# M401B.net
KiCad netlist of a schematic drawn in EAGLE
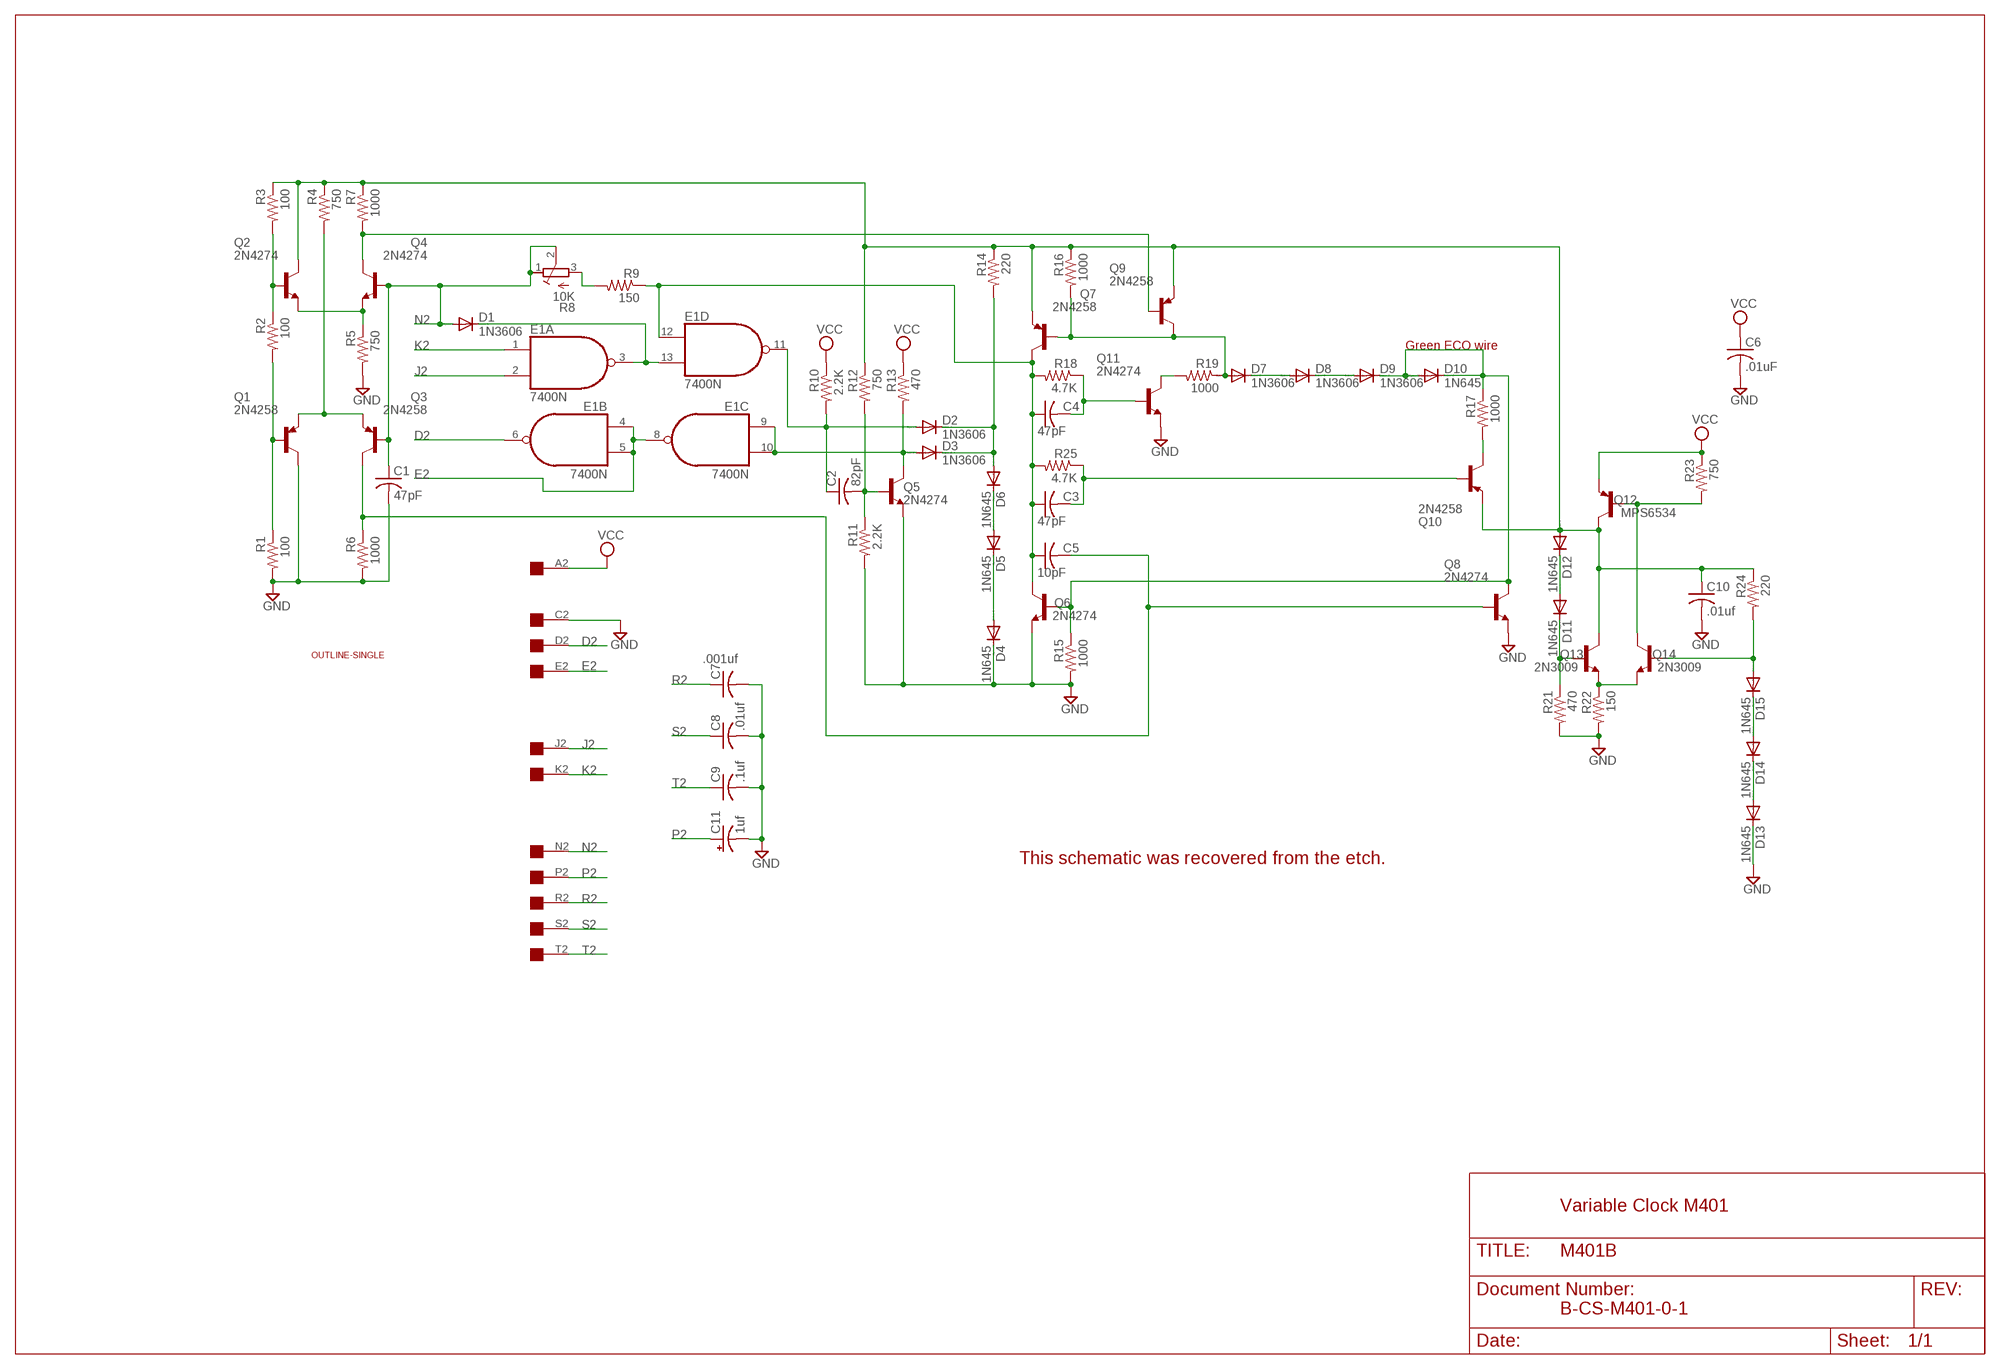
[diagram p0: schematic, sheet 1]

(export (version "E")
  (design (tool "Eeschema 10.0.6"))
  (components
    (comp (ref "C1")
      (value "47pF")
      (footprint "eagle-import:C050-025X075")
      (libsource (lib "eagle-import") (part "C-US050-025X075"))
    )
    (comp (ref "C2")
      (value "82pF")
      (footprint "eagle-import:C050-025X075")
      (libsource (lib "eagle-import") (part "C-US050-025X075"))
    )
    (comp (ref "C3")
      (value "47pF")
      (footprint "eagle-import:C050-025X075")
      (libsource (lib "eagle-import") (part "C-US050-025X075"))
    )
    (comp (ref "C4")
      (value "47pF")
      (footprint "eagle-import:C050-025X075")
      (libsource (lib "eagle-import") (part "C-US050-025X075"))
    )
    (comp (ref "C5")
      (value "10pF")
      (footprint "eagle-import:C225-062X268")
      (libsource (lib "eagle-import") (part "C-US225-062X268"))
    )
    (comp (ref "C6")
      (value ".01uF")
      (footprint "eagle-import:C050-025X075")
      (libsource (lib "eagle-import") (part "C-US050-025X075"))
    )
    (comp (ref "C7")
      (value ".001uf")
      (footprint "eagle-import:C050-025X075")
      (libsource (lib "eagle-import") (part "C-US050-025X075"))
    )
    (comp (ref "C8")
      (value ".01uf")
      (footprint "eagle-import:C225-062X268")
      (libsource (lib "eagle-import") (part "C-US225-062X268"))
    )
    (comp (ref "C9")
      (value ".1uf")
      (footprint "eagle-import:C275-093X316")
      (libsource (lib "eagle-import") (part "C-US275-093X316"))
    )
    (comp (ref "C10")
      (value ".01uf")
      (footprint "eagle-import:C050-025X075")
      (libsource (lib "eagle-import") (part "C-US050-025X075"))
    )
    (comp (ref "C11")
      (value "1uf")
      (footprint "eagle-import:E15-5")
      (libsource (lib "eagle-import") (part "CPOL-USE15-5AXIAL"))
    )
    (comp (ref "D1")
      (value "1N3606")
      (footprint "eagle-import:DO35-10")
      (libsource (lib "eagle-import") (part "1N4148DO35-10"))
    )
    (comp (ref "D2")
      (value "1N3606")
      (footprint "eagle-import:DO35-10")
      (libsource (lib "eagle-import") (part "1N4148DO35-10"))
    )
    (comp (ref "D3")
      (value "1N3606")
      (footprint "eagle-import:DO35-10")
      (libsource (lib "eagle-import") (part "1N4148DO35-10"))
    )
    (comp (ref "D4")
      (value "1N645")
      (footprint "eagle-import:DO35-10")
      (libsource (lib "eagle-import") (part "1N4148DO35-10"))
    )
    (comp (ref "D5")
      (value "1N645")
      (footprint "eagle-import:DO35-10")
      (libsource (lib "eagle-import") (part "1N4148DO35-10"))
    )
    (comp (ref "D6")
      (value "1N645")
      (footprint "eagle-import:DO35-10")
      (libsource (lib "eagle-import") (part "1N4148DO35-10"))
    )
    (comp (ref "D7")
      (value "1N3606")
      (footprint "eagle-import:DO35-10")
      (libsource (lib "eagle-import") (part "1N4148DO35-10"))
    )
    (comp (ref "D8")
      (value "1N3606")
      (footprint "eagle-import:DO35-10")
      (libsource (lib "eagle-import") (part "1N4148DO35-10"))
    )
    (comp (ref "D9")
      (value "1N3606")
      (footprint "eagle-import:DO35-10")
      (libsource (lib "eagle-import") (part "1N4148DO35-10"))
    )
    (comp (ref "D10")
      (value "1N645")
      (footprint "eagle-import:DO35-10")
      (libsource (lib "eagle-import") (part "1N4148DO35-10"))
    )
    (comp (ref "D11")
      (value "1N645")
      (footprint "eagle-import:DO35-10")
      (libsource (lib "eagle-import") (part "1N4148DO35-10"))
    )
    (comp (ref "D12")
      (value "1N645")
      (footprint "eagle-import:DO35-10")
      (libsource (lib "eagle-import") (part "1N4148DO35-10"))
    )
    (comp (ref "D13")
      (value "1N645")
      (footprint "eagle-import:DO35-10")
      (libsource (lib "eagle-import") (part "1N4148DO35-10"))
    )
    (comp (ref "D14")
      (value "1N645")
      (footprint "eagle-import:DO35-10")
      (libsource (lib "eagle-import") (part "1N4148DO35-10"))
    )
    (comp (ref "D15")
      (value "1N645")
      (footprint "eagle-import:DO35-10")
      (libsource (lib "eagle-import") (part "1N4148DO35-10"))
    )
    (comp (ref "E1")
      (value "7400N")
      (footprint "eagle-import:DIL14")
      (libsource (lib "eagle-import") (part "7400N"))
    )
    (comp (ref "Q1")
      (value "2N4258")
      (footprint "eagle-import:TO39")
      (libsource (lib "eagle-import") (part "-PNP-TO39-EBC2N3637"))
    )
    (comp (ref "Q2")
      (value "2N4274")
      (footprint "eagle-import:TO39")
      (libsource (lib "eagle-import") (part "-NPN-TO39-EBC2N3019"))
    )
    (comp (ref "Q3")
      (value "2N4258")
      (footprint "eagle-import:TO39")
      (libsource (lib "eagle-import") (part "-PNP-TO39-EBC2N3637"))
    )
    (comp (ref "Q4")
      (value "2N4274")
      (footprint "eagle-import:TO39")
      (libsource (lib "eagle-import") (part "-NPN-TO39-EBC2N3019"))
    )
    (comp (ref "Q5")
      (value "2N4274")
      (footprint "eagle-import:TO39")
      (libsource (lib "eagle-import") (part "-NPN-TO39-EBC2N3019"))
    )
    (comp (ref "Q6")
      (value "2N4274")
      (footprint "eagle-import:TO39")
      (libsource (lib "eagle-import") (part "-NPN-TO39-EBC2N3019"))
    )
    (comp (ref "Q7")
      (value "2N4258")
      (footprint "eagle-import:TO39")
      (libsource (lib "eagle-import") (part "-PNP-TO39-EBC2N3637"))
    )
    (comp (ref "Q8")
      (value "2N4274")
      (footprint "eagle-import:TO39")
      (libsource (lib "eagle-import") (part "-NPN-TO39-EBC2N3019"))
    )
    (comp (ref "Q9")
      (value "2N4258")
      (footprint "eagle-import:TO39")
      (libsource (lib "eagle-import") (part "-PNP-TO39-EBC2N3637"))
    )
    (comp (ref "Q10")
      (value "2N4258")
      (footprint "eagle-import:TO39")
      (libsource (lib "eagle-import") (part "-PNP-TO39-EBC2N3637"))
    )
    (comp (ref "Q11")
      (value "2N4274")
      (footprint "eagle-import:TO39")
      (libsource (lib "eagle-import") (part "-NPN-TO39-EBC2N3019"))
    )
    (comp (ref "Q12")
      (value "MPS6534")
      (footprint "eagle-import:TO39")
      (libsource (lib "eagle-import") (part "-PNP-TO39-EBC2N3637"))
    )
    (comp (ref "Q13")
      (value "2N3009")
      (footprint "eagle-import:TO39")
      (libsource (lib "eagle-import") (part "-NPN-TO39-EBC2N3019"))
    )
    (comp (ref "Q14")
      (value "2N3009")
      (footprint "eagle-import:TO39")
      (libsource (lib "eagle-import") (part "-NPN-TO39-EBC2N3019"))
    )
    (comp (ref "R1")
      (value "100")
      (footprint "eagle-import:0207_10")
      (libsource (lib "eagle-import") (part "R-US_0207/10"))
    )
    (comp (ref "R2")
      (value "100")
      (footprint "eagle-import:0207_10")
      (libsource (lib "eagle-import") (part "R-US_0207/10"))
    )
    (comp (ref "R3")
      (value "100")
      (footprint "eagle-import:0207_10")
      (libsource (lib "eagle-import") (part "R-US_0207/10"))
    )
    (comp (ref "R4")
      (value "750")
      (footprint "eagle-import:0207_10")
      (libsource (lib "eagle-import") (part "R-US_0207/10"))
    )
    (comp (ref "R5")
      (value "750")
      (footprint "eagle-import:0207_10")
      (libsource (lib "eagle-import") (part "R-US_0207/10"))
    )
    (comp (ref "R6")
      (value "1000")
      (footprint "eagle-import:0207_10")
      (libsource (lib "eagle-import") (part "R-US_0207/10"))
    )
    (comp (ref "R7")
      (value "1000")
      (footprint "eagle-import:0207_10")
      (libsource (lib "eagle-import") (part "R-US_0207/10"))
    )
    (comp (ref "R8")
      (value "10K")
      (footprint "eagle-import:3006Y")
      (libsource (lib "eagle-import") (part "275P"))
    )
    (comp (ref "R9")
      (value "150")
      (footprint "eagle-import:0207_10")
      (libsource (lib "eagle-import") (part "R-US_0207/10"))
    )
    (comp (ref "R10")
      (value "2.2K")
      (footprint "eagle-import:0207_10")
      (libsource (lib "eagle-import") (part "R-US_0207/10"))
    )
    (comp (ref "R11")
      (value "2.2K")
      (footprint "eagle-import:0207_10")
      (libsource (lib "eagle-import") (part "R-US_0207/10"))
    )
    (comp (ref "R12")
      (value "750")
      (footprint "eagle-import:0207_10")
      (libsource (lib "eagle-import") (part "R-US_0207/10"))
    )
    (comp (ref "R13")
      (value "470")
      (footprint "eagle-import:0207_10")
      (libsource (lib "eagle-import") (part "R-US_0207/10"))
    )
    (comp (ref "R14")
      (value "220")
      (footprint "eagle-import:0207_10")
      (libsource (lib "eagle-import") (part "R-US_0207/10"))
    )
    (comp (ref "R15")
      (value "1000")
      (footprint "eagle-import:0207_10")
      (libsource (lib "eagle-import") (part "R-US_0207/10"))
    )
    (comp (ref "R16")
      (value "1000")
      (footprint "eagle-import:0207_10")
      (libsource (lib "eagle-import") (part "R-US_0207/10"))
    )
    (comp (ref "R17")
      (value "1000")
      (footprint "eagle-import:0207_10")
      (libsource (lib "eagle-import") (part "R-US_0207/10"))
    )
    (comp (ref "R18")
      (value "4.7K")
      (footprint "eagle-import:0207_10")
      (libsource (lib "eagle-import") (part "R-US_0207/10"))
    )
    (comp (ref "R19")
      (value "1000")
      (footprint "eagle-import:0207_10")
      (libsource (lib "eagle-import") (part "R-US_0207/10"))
    )
    (comp (ref "R21")
      (value "470")
      (footprint "eagle-import:0207_10")
      (libsource (lib "eagle-import") (part "R-US_0207/10"))
    )
    (comp (ref "R22")
      (value "150")
      (footprint "eagle-import:0207_10")
      (libsource (lib "eagle-import") (part "R-US_0207/10"))
    )
    (comp (ref "R23")
      (value "750")
      (footprint "eagle-import:0207_10")
      (libsource (lib "eagle-import") (part "R-US_0207/10"))
    )
    (comp (ref "R24")
      (value "220")
      (footprint "eagle-import:0207_10")
      (libsource (lib "eagle-import") (part "R-US_0207/10"))
    )
    (comp (ref "R25")
      (value "4.7K")
      (footprint "eagle-import:0207_10")
      (libsource (lib "eagle-import") (part "R-US_0207/10"))
    )
    (comp (ref "U$1")
      (value "OUTLINE-SINGLE")
      (footprint "eagle-import:SINGLE")
      (libsource (lib "eagle-import") (part "OUTLINE-SINGLE"))
    )
    (comp (ref "U$2")
      (value "EDGE-1")
      (footprint "eagle-import:EDGE-CON1")
      (libsource (lib "eagle-import") (part "EDGE-1"))
    )
  )
  (nets
    (net (code "1") (name "/D2") (class "Default")
      (node (ref "E1") (pin "6") (pinfunction "O_6") (pintype "output"))
      (node (ref "U$2") (pin "D2") (pinfunction "1_D2") (pintype "bidirectional"))
    )
    (net (code "2") (name "/E2") (class "Default")
      (node (ref "E1") (pin "4") (pinfunction "I0_4") (pintype "input"))
      (node (ref "E1") (pin "5") (pinfunction "I1_5") (pintype "input"))
      (node (ref "E1") (pin "8") (pinfunction "O_8") (pintype "output"))
      (node (ref "U$2") (pin "E2") (pinfunction "1_E2") (pintype "bidirectional"))
    )
    (net (code "3") (name "/J2") (class "Default")
      (node (ref "E1") (pin "2") (pinfunction "I1_2") (pintype "input"))
      (node (ref "U$2") (pin "J2") (pinfunction "1_J2") (pintype "bidirectional"))
    )
    (net (code "4") (name "/K2") (class "Default")
      (node (ref "E1") (pin "1") (pinfunction "I0_1") (pintype "input"))
      (node (ref "U$2") (pin "K2") (pinfunction "1_K2") (pintype "bidirectional"))
    )
    (net (code "5") (name "/N2") (class "Default")
      (node (ref "C1") (pin "1") (pinfunction "1_1") (pintype "passive"))
      (node (ref "D1") (pin "A") (pinfunction "A_A") (pintype "passive"))
      (node (ref "Q3") (pin "2") (pinfunction "B_2") (pintype "passive"))
      (node (ref "Q4") (pin "2") (pinfunction "B_2") (pintype "passive"))
      (node (ref "R8") (pin "1") (pinfunction "A_1") (pintype "passive"))
      (node (ref "R8") (pin "2") (pinfunction "S_2") (pintype "passive"))
      (node (ref "U$2") (pin "N2") (pinfunction "1_N2") (pintype "bidirectional"))
    )
    (net (code "6") (name "/P2") (class "Default")
      (node (ref "C11") (pin "+") (pinfunction "+_+") (pintype "passive"))
      (node (ref "U$2") (pin "P2") (pinfunction "1_P2") (pintype "bidirectional"))
    )
    (net (code "7") (name "/R2") (class "Default")
      (node (ref "C7") (pin "1") (pinfunction "1_1") (pintype "passive"))
      (node (ref "U$2") (pin "R2") (pinfunction "1_R2") (pintype "bidirectional"))
    )
    (net (code "8") (name "/S2") (class "Default")
      (node (ref "C8") (pin "1") (pinfunction "1_1") (pintype "passive"))
      (node (ref "U$2") (pin "S2") (pinfunction "1_S2") (pintype "bidirectional"))
    )
    (net (code "9") (name "/T2") (class "Default")
      (node (ref "C9") (pin "1") (pinfunction "1_1") (pintype "passive"))
      (node (ref "U$2") (pin "T2") (pinfunction "1_T2") (pintype "bidirectional"))
    )
    (net (code "10") (name "GND") (class "Default")
      (node (ref "C1") (pin "2") (pinfunction "2_2") (pintype "passive"))
      (node (ref "C10") (pin "2") (pinfunction "2_2") (pintype "passive"))
      (node (ref "C11") (pin "-") (pinfunction "-_-") (pintype "passive"))
      (node (ref "C6") (pin "2") (pinfunction "2_2") (pintype "passive"))
      (node (ref "C7") (pin "2") (pinfunction "2_2") (pintype "passive"))
      (node (ref "C8") (pin "2") (pinfunction "2_2") (pintype "passive"))
      (node (ref "C9") (pin "2") (pinfunction "2_2") (pintype "passive"))
      (node (ref "D13") (pin "C") (pinfunction "C_C") (pintype "passive"))
      (node (ref "D4") (pin "C") (pinfunction "C_C") (pintype "passive"))
      (node (ref "Q1") (pin "3") (pinfunction "C_3") (pintype "passive"))
      (node (ref "Q11") (pin "1") (pinfunction "E_1") (pintype "passive"))
      (node (ref "Q5") (pin "1") (pinfunction "E_1") (pintype "passive"))
      (node (ref "Q6") (pin "1") (pinfunction "E_1") (pintype "passive"))
      (node (ref "Q8") (pin "1") (pinfunction "E_1") (pintype "passive"))
      (node (ref "R1") (pin "2") (pinfunction "2_2") (pintype "passive"))
      (node (ref "R11") (pin "2") (pinfunction "2_2") (pintype "passive"))
      (node (ref "R15") (pin "2") (pinfunction "2_2") (pintype "passive"))
      (node (ref "R21") (pin "2") (pinfunction "2_2") (pintype "passive"))
      (node (ref "R22") (pin "2") (pinfunction "2_2") (pintype "passive"))
      (node (ref "R5") (pin "2") (pinfunction "2_2") (pintype "passive"))
      (node (ref "R6") (pin "2") (pinfunction "2_2") (pintype "passive"))
      (node (ref "U$2") (pin "C2") (pinfunction "1_C2") (pintype "bidirectional"))
    )
    (net (code "11") (name "Net-(D2-PadC)") (class "Default")
      (node (ref "D2") (pin "C") (pinfunction "C_C") (pintype "passive"))
      (node (ref "D3") (pin "C") (pinfunction "C_C") (pintype "passive"))
      (node (ref "D6") (pin "A") (pinfunction "A_A") (pintype "passive"))
      (node (ref "R14") (pin "2") (pinfunction "2_2") (pintype "passive"))
    )
    (net (code "12") (name "Net-(D4-PadA)") (class "Default")
      (node (ref "D4") (pin "A") (pinfunction "A_A") (pintype "passive"))
      (node (ref "D5") (pin "C") (pinfunction "C_C") (pintype "passive"))
    )
    (net (code "13") (name "Net-(D5-PadA)") (class "Default")
      (node (ref "D5") (pin "A") (pinfunction "A_A") (pintype "passive"))
      (node (ref "D6") (pin "C") (pinfunction "C_C") (pintype "passive"))
    )
    (net (code "14") (name "Net-(D7-PadC)") (class "Default")
      (node (ref "D7") (pin "C") (pinfunction "C_C") (pintype "passive"))
      (node (ref "D8") (pin "A") (pinfunction "A_A") (pintype "passive"))
    )
    (net (code "15") (name "Net-(D8-PadC)") (class "Default")
      (node (ref "D8") (pin "C") (pinfunction "C_C") (pintype "passive"))
      (node (ref "D9") (pin "A") (pinfunction "A_A") (pintype "passive"))
    )
    (net (code "16") (name "Net-(D11-PadA)") (class "Default")
      (node (ref "D11") (pin "A") (pinfunction "A_A") (pintype "passive"))
      (node (ref "D12") (pin "C") (pinfunction "C_C") (pintype "passive"))
    )
    (net (code "17") (name "Net-(D13-PadA)") (class "Default")
      (node (ref "D13") (pin "A") (pinfunction "A_A") (pintype "passive"))
      (node (ref "D14") (pin "C") (pinfunction "C_C") (pintype "passive"))
    )
    (net (code "18") (name "Net-(D14-PadA)") (class "Default")
      (node (ref "D14") (pin "A") (pinfunction "A_A") (pintype "passive"))
      (node (ref "D15") (pin "C") (pinfunction "C_C") (pintype "passive"))
    )
    (net (code "19") (name "Net-(E1A-O)") (class "Default")
      (node (ref "D1") (pin "C") (pinfunction "C_C") (pintype "passive"))
      (node (ref "E1") (pin "13") (pinfunction "I1_13") (pintype "input"))
      (node (ref "E1") (pin "3") (pinfunction "O_3") (pintype "output"))
    )
    (net (code "20") (name "Net-(E1C-I0)") (class "Default")
      (node (ref "D3") (pin "A") (pinfunction "A_A") (pintype "passive"))
      (node (ref "E1") (pin "10") (pinfunction "I1_10") (pintype "input"))
      (node (ref "E1") (pin "9") (pinfunction "I0_9") (pintype "input"))
      (node (ref "Q5") (pin "3") (pinfunction "C_3") (pintype "passive"))
      (node (ref "R13") (pin "2") (pinfunction "2_2") (pintype "passive"))
    )
    (net (code "21") (name "Net-(E1D-I0)") (class "Default")
      (node (ref "C3") (pin "1") (pinfunction "1_1") (pintype "passive"))
      (node (ref "C4") (pin "1") (pinfunction "1_1") (pintype "passive"))
      (node (ref "C5") (pin "1") (pinfunction "1_1") (pintype "passive"))
      (node (ref "E1") (pin "12") (pinfunction "I0_12") (pintype "input"))
      (node (ref "Q6") (pin "3") (pinfunction "C_3") (pintype "passive"))
      (node (ref "Q7") (pin "3") (pinfunction "C_3") (pintype "passive"))
      (node (ref "R18") (pin "2") (pinfunction "2_2") (pintype "passive"))
      (node (ref "R25") (pin "2") (pinfunction "2_2") (pintype "passive"))
      (node (ref "R9") (pin "1") (pinfunction "1_1") (pintype "passive"))
    )
    (net (code "22") (name "Net-(E1D-O)") (class "Default")
      (node (ref "C2") (pin "1") (pinfunction "1_1") (pintype "passive"))
      (node (ref "D2") (pin "A") (pinfunction "A_A") (pintype "passive"))
      (node (ref "E1") (pin "11") (pinfunction "O_11") (pintype "output"))
      (node (ref "R10") (pin "2") (pinfunction "2_2") (pintype "passive"))
    )
    (net (code "23") (name "Net-(Q1-B)") (class "Default")
      (node (ref "Q1") (pin "2") (pinfunction "B_2") (pintype "passive"))
      (node (ref "R1") (pin "1") (pinfunction "1_1") (pintype "passive"))
      (node (ref "R2") (pin "2") (pinfunction "2_2") (pintype "passive"))
    )
    (net (code "24") (name "Net-(Q1-E)") (class "Default")
      (node (ref "Q1") (pin "1") (pinfunction "E_1") (pintype "passive"))
      (node (ref "Q3") (pin "1") (pinfunction "E_1") (pintype "passive"))
      (node (ref "R4") (pin "2") (pinfunction "2_2") (pintype "passive"))
    )
    (net (code "25") (name "Net-(Q2-B)") (class "Default")
      (node (ref "Q2") (pin "2") (pinfunction "B_2") (pintype "passive"))
      (node (ref "R2") (pin "1") (pinfunction "1_1") (pintype "passive"))
      (node (ref "R3") (pin "2") (pinfunction "2_2") (pintype "passive"))
    )
    (net (code "26") (name "Net-(Q2-E)") (class "Default")
      (node (ref "Q2") (pin "1") (pinfunction "E_1") (pintype "passive"))
      (node (ref "Q4") (pin "1") (pinfunction "E_1") (pintype "passive"))
      (node (ref "R5") (pin "1") (pinfunction "1_1") (pintype "passive"))
    )
    (net (code "27") (name "Net-(Q3-C)") (class "Default")
      (node (ref "C5") (pin "2") (pinfunction "2_2") (pintype "passive"))
      (node (ref "Q3") (pin "3") (pinfunction "C_3") (pintype "passive"))
      (node (ref "Q8") (pin "2") (pinfunction "B_2") (pintype "passive"))
      (node (ref "R6") (pin "1") (pinfunction "1_1") (pintype "passive"))
    )
    (net (code "28") (name "Net-(Q4-C)") (class "Default")
      (node (ref "Q4") (pin "3") (pinfunction "C_3") (pintype "passive"))
      (node (ref "Q9") (pin "2") (pinfunction "B_2") (pintype "passive"))
      (node (ref "R7") (pin "2") (pinfunction "2_2") (pintype "passive"))
    )
    (net (code "29") (name "Net-(Q5-B)") (class "Default")
      (node (ref "C2") (pin "2") (pinfunction "2_2") (pintype "passive"))
      (node (ref "Q5") (pin "2") (pinfunction "B_2") (pintype "passive"))
      (node (ref "R11") (pin "1") (pinfunction "1_1") (pintype "passive"))
      (node (ref "R12") (pin "2") (pinfunction "2_2") (pintype "passive"))
    )
    (net (code "30") (name "Net-(Q6-B)") (class "Default")
      (node (ref "D10") (pin "A") (pinfunction "A_A") (pintype "passive"))
      (node (ref "D10") (pin "C") (pinfunction "C_C") (pintype "passive"))
      (node (ref "D9") (pin "C") (pinfunction "C_C") (pintype "passive"))
      (node (ref "Q6") (pin "2") (pinfunction "B_2") (pintype "passive"))
      (node (ref "Q8") (pin "3") (pinfunction "C_3") (pintype "passive"))
      (node (ref "R15") (pin "1") (pinfunction "1_1") (pintype "passive"))
      (node (ref "R17") (pin "1") (pinfunction "1_1") (pintype "passive"))
    )
    (net (code "31") (name "Net-(Q7-B)") (class "Default")
      (node (ref "D7") (pin "A") (pinfunction "A_A") (pintype "passive"))
      (node (ref "Q7") (pin "2") (pinfunction "B_2") (pintype "passive"))
      (node (ref "Q9") (pin "3") (pinfunction "C_3") (pintype "passive"))
      (node (ref "R16") (pin "2") (pinfunction "2_2") (pintype "passive"))
      (node (ref "R19") (pin "1") (pinfunction "1_1") (pintype "passive"))
    )
    (net (code "32") (name "Net-(Q10-B)") (class "Default")
      (node (ref "C3") (pin "2") (pinfunction "2_2") (pintype "passive"))
      (node (ref "Q10") (pin "2") (pinfunction "B_2") (pintype "passive"))
      (node (ref "R25") (pin "1") (pinfunction "1_1") (pintype "passive"))
    )
    (net (code "33") (name "Net-(Q10-C)") (class "Default")
      (node (ref "Q10") (pin "3") (pinfunction "C_3") (pintype "passive"))
      (node (ref "R17") (pin "2") (pinfunction "2_2") (pintype "passive"))
    )
    (net (code "34") (name "Net-(Q10-E)") (class "Default")
      (node (ref "C10") (pin "1") (pinfunction "1_1") (pintype "passive"))
      (node (ref "D12") (pin "A") (pinfunction "A_A") (pintype "passive"))
      (node (ref "Q10") (pin "1") (pinfunction "E_1") (pintype "passive"))
      (node (ref "Q12") (pin "3") (pinfunction "C_3") (pintype "passive"))
      (node (ref "Q13") (pin "3") (pinfunction "C_3") (pintype "passive"))
      (node (ref "Q2") (pin "3") (pinfunction "C_3") (pintype "passive"))
      (node (ref "Q7") (pin "1") (pinfunction "E_1") (pintype "passive"))
      (node (ref "Q9") (pin "1") (pinfunction "E_1") (pintype "passive"))
      (node (ref "R12") (pin "1") (pinfunction "1_1") (pintype "passive"))
      (node (ref "R14") (pin "1") (pinfunction "1_1") (pintype "passive"))
      (node (ref "R16") (pin "1") (pinfunction "1_1") (pintype "passive"))
      (node (ref "R24") (pin "1") (pinfunction "1_1") (pintype "passive"))
      (node (ref "R3") (pin "1") (pinfunction "1_1") (pintype "passive"))
      (node (ref "R4") (pin "1") (pinfunction "1_1") (pintype "passive"))
      (node (ref "R7") (pin "1") (pinfunction "1_1") (pintype "passive"))
    )
    (net (code "35") (name "Net-(Q11-B)") (class "Default")
      (node (ref "C4") (pin "2") (pinfunction "2_2") (pintype "passive"))
      (node (ref "Q11") (pin "2") (pinfunction "B_2") (pintype "passive"))
      (node (ref "R18") (pin "1") (pinfunction "1_1") (pintype "passive"))
    )
    (net (code "36") (name "Net-(Q11-C)") (class "Default")
      (node (ref "Q11") (pin "3") (pinfunction "C_3") (pintype "passive"))
      (node (ref "R19") (pin "2") (pinfunction "2_2") (pintype "passive"))
    )
    (net (code "37") (name "Net-(Q12-B)") (class "Default")
      (node (ref "Q12") (pin "2") (pinfunction "B_2") (pintype "passive"))
      (node (ref "Q14") (pin "3") (pinfunction "C_3") (pintype "passive"))
      (node (ref "R23") (pin "2") (pinfunction "2_2") (pintype "passive"))
    )
    (net (code "38") (name "Net-(Q13-B)") (class "Default")
      (node (ref "D11") (pin "C") (pinfunction "C_C") (pintype "passive"))
      (node (ref "Q13") (pin "2") (pinfunction "B_2") (pintype "passive"))
      (node (ref "R21") (pin "1") (pinfunction "1_1") (pintype "passive"))
    )
    (net (code "39") (name "Net-(Q13-E)") (class "Default")
      (node (ref "Q13") (pin "1") (pinfunction "E_1") (pintype "passive"))
      (node (ref "Q14") (pin "1") (pinfunction "E_1") (pintype "passive"))
      (node (ref "R22") (pin "1") (pinfunction "1_1") (pintype "passive"))
    )
    (net (code "40") (name "Net-(Q14-B)") (class "Default")
      (node (ref "D15") (pin "A") (pinfunction "A_A") (pintype "passive"))
      (node (ref "Q14") (pin "2") (pinfunction "B_2") (pintype "passive"))
      (node (ref "R24") (pin "2") (pinfunction "2_2") (pintype "passive"))
    )
    (net (code "41") (name "Net-(R8-E)") (class "Default")
      (node (ref "R8") (pin "3") (pinfunction "E_3") (pintype "passive"))
      (node (ref "R9") (pin "2") (pinfunction "2_2") (pintype "passive"))
    )
    (net (code "42") (name "VCC") (class "Default")
      (node (ref "C6") (pin "1") (pinfunction "1_1") (pintype "passive"))
      (node (ref "Q12") (pin "1") (pinfunction "E_1") (pintype "passive"))
      (node (ref "R10") (pin "1") (pinfunction "1_1") (pintype "passive"))
      (node (ref "R13") (pin "1") (pinfunction "1_1") (pintype "passive"))
      (node (ref "R23") (pin "1") (pinfunction "1_1") (pintype "passive"))
      (node (ref "U$2") (pin "A2") (pinfunction "1_A2") (pintype "bidirectional"))
    )
  )
)
